# switch.net
KiCad netlist of a schematic drawn in EAGLE
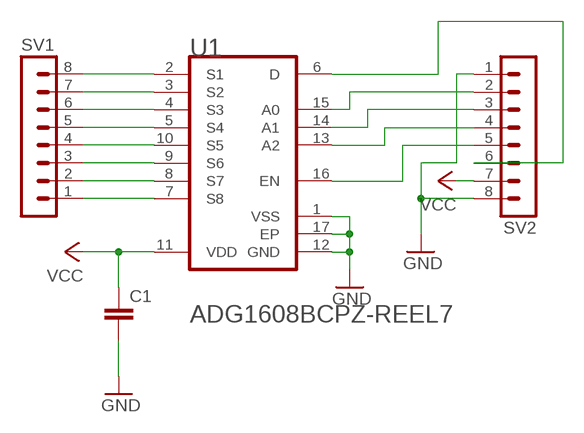
[diagram p0: schematic, sheet 1]

(export (version "E")
  (design (tool "Eeschema 10.0.6"))
  (components
    (comp (ref "C1")
      (value "C-EUC0805")
      (footprint "eagle-import:C0805")
      (libsource (lib "eagle-import") (part "C-EUC0805"))
    )
    (comp (ref "SV1")
      (value "MA08-1")
      (footprint "eagle-import:MA08-1")
      (libsource (lib "eagle-import") (part "MA08-1"))
    )
    (comp (ref "SV2")
      (value "MA08-1")
      (footprint "eagle-import:MA08-1")
      (libsource (lib "eagle-import") (part "MA08-1"))
    )
    (comp (ref "U1")
      (value "ANALOG_DEVICES_ADG1608BCPZ-REEL7ANALOG_DEVICES_ADG1608BCPZ-REEL7_0_1")
      (footprint "eagle-import:ANALOG_DEVICES_ADG1608BCPZ-REEL7_1")
      (fields (field (name "MF") "Analog Devices") (field (name "MPN") "ADG1608BCPZ-REEL7"))
      (libsource (lib "eagle-import") (part "ANALOG_DEVICES_ADG1608BCPZ-REEL7ANALOG_DEVICES_ADG1608BCPZ-REEL7_0_1"))
    )
  )
  (nets
    (net (code "1") (name "GND") (class "Default")
      (node (ref "C1") (pin "2") (pinfunction "2_2") (pintype "passive"))
      (node (ref "SV2") (pin "1") (pinfunction "1_1") (pintype "passive"))
      (node (ref "SV2") (pin "8") (pinfunction "8_8") (pintype "passive"))
      (node (ref "U1") (pin "1") (pinfunction "VSS_1") (pintype "power_in"))
      (node (ref "U1") (pin "12") (pinfunction "GND_12") (pintype "power_in"))
      (node (ref "U1") (pin "17") (pinfunction "EP_17") (pintype "power_in"))
    )
    (net (code "2") (name "Net-(U1-A0)") (class "Default")
      (node (ref "SV2") (pin "2") (pinfunction "2_2") (pintype "passive"))
      (node (ref "U1") (pin "15") (pinfunction "A0_15") (pintype "input"))
    )
    (net (code "3") (name "Net-(U1-A1)") (class "Default")
      (node (ref "SV2") (pin "3") (pinfunction "3_3") (pintype "passive"))
      (node (ref "U1") (pin "14") (pinfunction "A1_14") (pintype "input"))
    )
    (net (code "4") (name "Net-(U1-A2)") (class "Default")
      (node (ref "SV2") (pin "4") (pinfunction "4_4") (pintype "passive"))
      (node (ref "U1") (pin "13") (pinfunction "A2_13") (pintype "input"))
    )
    (net (code "5") (name "Net-(U1-D)") (class "Default")
      (node (ref "SV2") (pin "6") (pinfunction "6_6") (pintype "passive"))
      (node (ref "U1") (pin "6") (pinfunction "D_6") (pintype "passive"))
    )
    (net (code "6") (name "Net-(U1-EN)") (class "Default")
      (node (ref "SV2") (pin "5") (pinfunction "5_5") (pintype "passive"))
      (node (ref "U1") (pin "16") (pinfunction "EN_16") (pintype "input"))
    )
    (net (code "7") (name "Net-(U1-S1)") (class "Default")
      (node (ref "SV1") (pin "8") (pinfunction "8_8") (pintype "passive"))
      (node (ref "U1") (pin "2") (pinfunction "S1_2") (pintype "passive"))
    )
    (net (code "8") (name "Net-(U1-S2)") (class "Default")
      (node (ref "SV1") (pin "7") (pinfunction "7_7") (pintype "passive"))
      (node (ref "U1") (pin "3") (pinfunction "S2_3") (pintype "passive"))
    )
    (net (code "9") (name "Net-(U1-S3)") (class "Default")
      (node (ref "SV1") (pin "6") (pinfunction "6_6") (pintype "passive"))
      (node (ref "U1") (pin "4") (pinfunction "S3_4") (pintype "passive"))
    )
    (net (code "10") (name "Net-(U1-S4)") (class "Default")
      (node (ref "SV1") (pin "5") (pinfunction "5_5") (pintype "passive"))
      (node (ref "U1") (pin "5") (pinfunction "S4_5") (pintype "passive"))
    )
    (net (code "11") (name "Net-(U1-S5)") (class "Default")
      (node (ref "SV1") (pin "4") (pinfunction "4_4") (pintype "passive"))
      (node (ref "U1") (pin "10") (pinfunction "S5_10") (pintype "passive"))
    )
    (net (code "12") (name "Net-(U1-S6)") (class "Default")
      (node (ref "SV1") (pin "3") (pinfunction "3_3") (pintype "passive"))
      (node (ref "U1") (pin "9") (pinfunction "S6_9") (pintype "passive"))
    )
    (net (code "13") (name "Net-(U1-S7)") (class "Default")
      (node (ref "SV1") (pin "2") (pinfunction "2_2") (pintype "passive"))
      (node (ref "U1") (pin "8") (pinfunction "S7_8") (pintype "passive"))
    )
    (net (code "14") (name "Net-(U1-S8)") (class "Default")
      (node (ref "SV1") (pin "1") (pinfunction "1_1") (pintype "passive"))
      (node (ref "U1") (pin "7") (pinfunction "S8_7") (pintype "passive"))
    )
    (net (code "15") (name "VCC") (class "Default")
      (node (ref "C1") (pin "1") (pinfunction "1_1") (pintype "passive"))
      (node (ref "SV2") (pin "7") (pinfunction "7_7") (pintype "passive"))
      (node (ref "U1") (pin "11") (pinfunction "VDD_11") (pintype "power_in"))
    )
  )
)
